# sensorboard.net
KiCad netlist of a schematic drawn in EAGLE
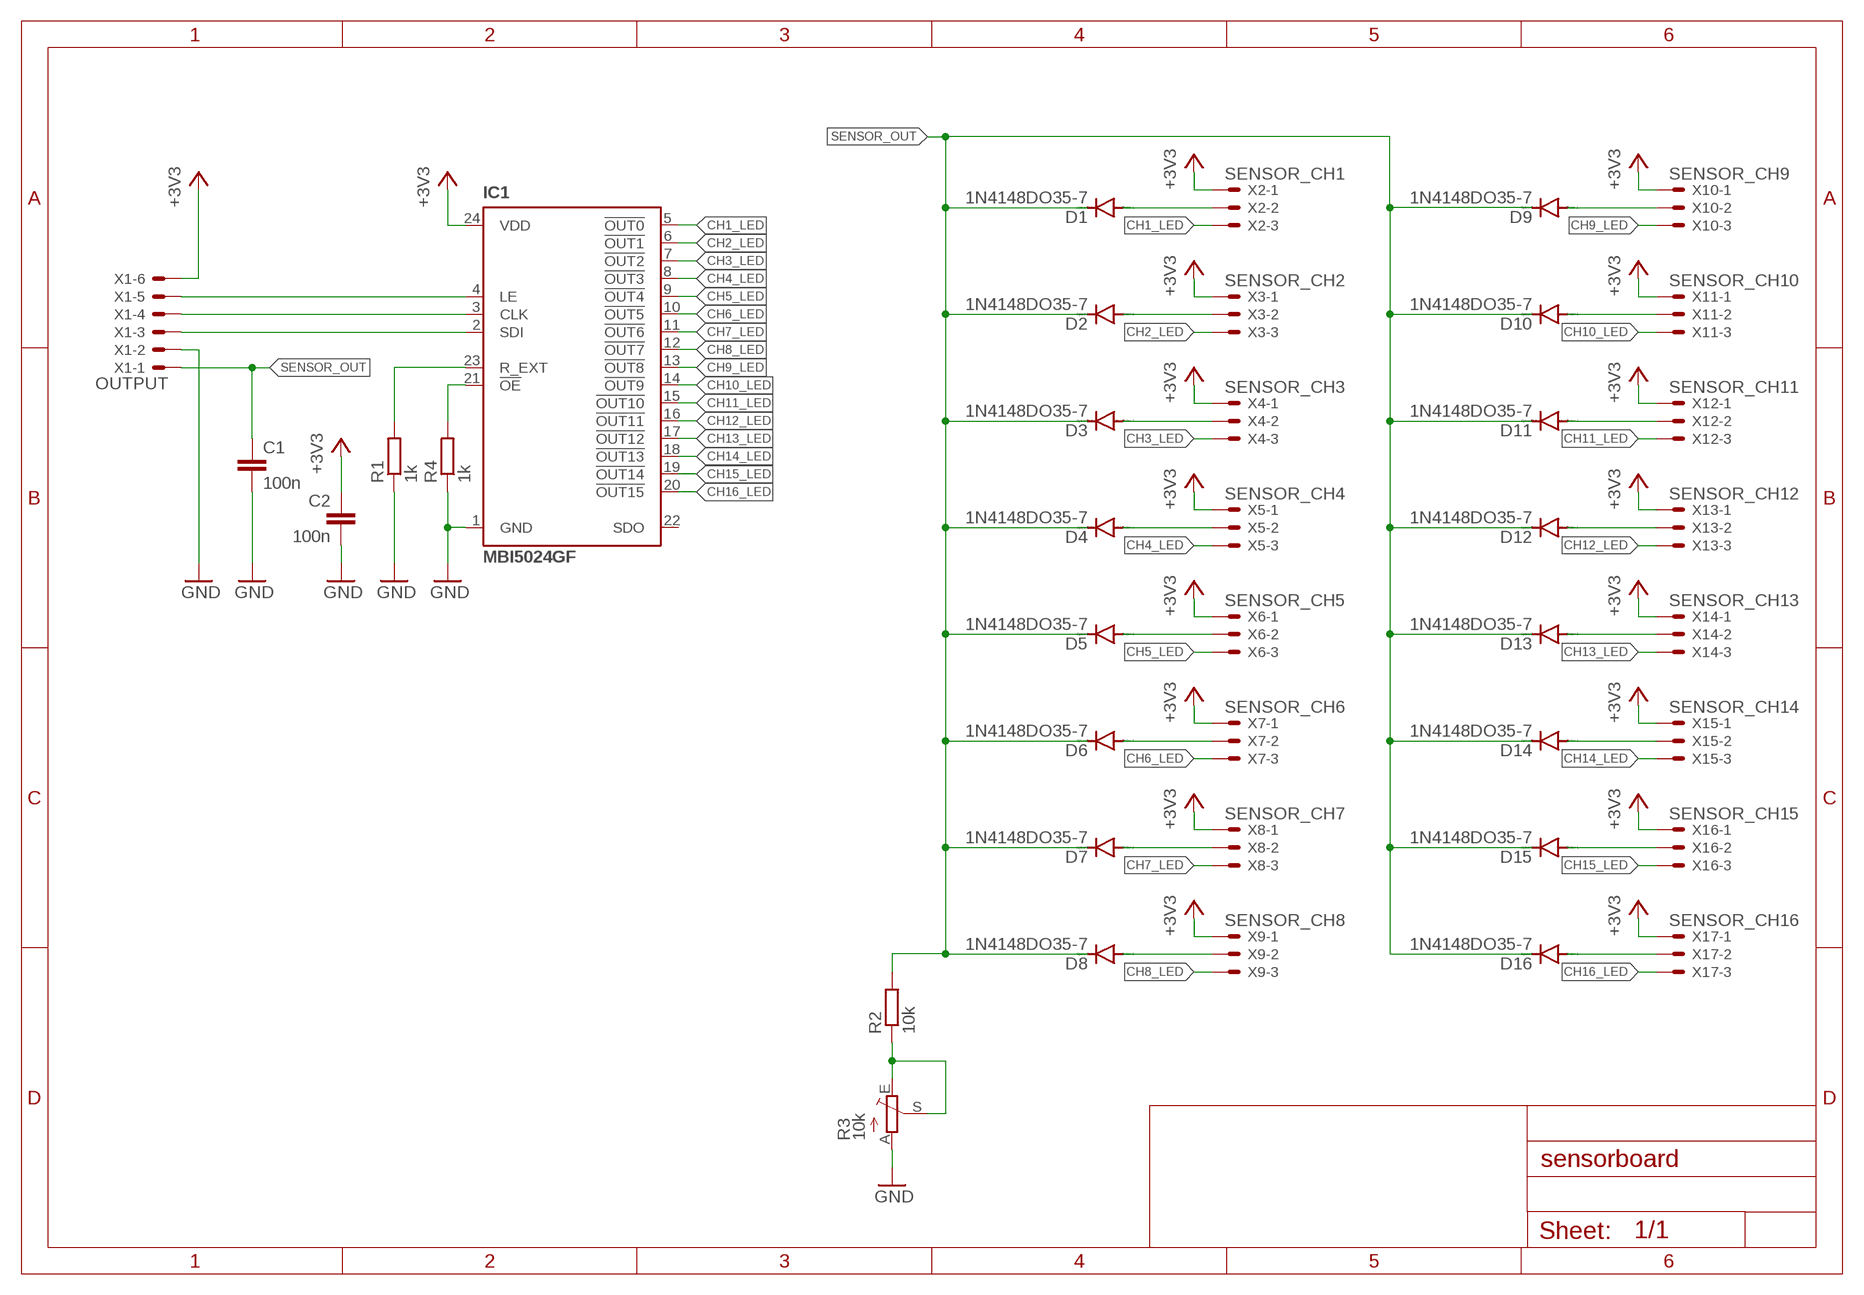
[diagram p0: schematic, sheet 1]

(export (version "E")
  (design (tool "Eeschema 10.0.6"))
  (components
    (comp (ref "C1")
      (value "100n")
      (footprint "eagle-import:C050-024X044")
      (libsource (lib "eagle-import") (part "C-EU050-024X044"))
    )
    (comp (ref "C2")
      (value "100n")
      (footprint "eagle-import:C050-024X044")
      (libsource (lib "eagle-import") (part "C-EU050-024X044"))
    )
    (comp (ref "D1")
      (value "1N4148DO35-7")
      (footprint "eagle-import:DO35-7")
      (libsource (lib "eagle-import") (part "1N4148DO35-7"))
    )
    (comp (ref "D2")
      (value "1N4148DO35-7")
      (footprint "eagle-import:DO35-7")
      (libsource (lib "eagle-import") (part "1N4148DO35-7"))
    )
    (comp (ref "D3")
      (value "1N4148DO35-7")
      (footprint "eagle-import:DO35-7")
      (libsource (lib "eagle-import") (part "1N4148DO35-7"))
    )
    (comp (ref "D4")
      (value "1N4148DO35-7")
      (footprint "eagle-import:DO35-7")
      (libsource (lib "eagle-import") (part "1N4148DO35-7"))
    )
    (comp (ref "D5")
      (value "1N4148DO35-7")
      (footprint "eagle-import:DO35-7")
      (libsource (lib "eagle-import") (part "1N4148DO35-7"))
    )
    (comp (ref "D6")
      (value "1N4148DO35-7")
      (footprint "eagle-import:DO35-7")
      (libsource (lib "eagle-import") (part "1N4148DO35-7"))
    )
    (comp (ref "D7")
      (value "1N4148DO35-7")
      (footprint "eagle-import:DO35-7")
      (libsource (lib "eagle-import") (part "1N4148DO35-7"))
    )
    (comp (ref "D8")
      (value "1N4148DO35-7")
      (footprint "eagle-import:DO35-7")
      (libsource (lib "eagle-import") (part "1N4148DO35-7"))
    )
    (comp (ref "D9")
      (value "1N4148DO35-7")
      (footprint "eagle-import:DO35-7")
      (libsource (lib "eagle-import") (part "1N4148DO35-7"))
    )
    (comp (ref "D10")
      (value "1N4148DO35-7")
      (footprint "eagle-import:DO35-7")
      (libsource (lib "eagle-import") (part "1N4148DO35-7"))
    )
    (comp (ref "D11")
      (value "1N4148DO35-7")
      (footprint "eagle-import:DO35-7")
      (libsource (lib "eagle-import") (part "1N4148DO35-7"))
    )
    (comp (ref "D12")
      (value "1N4148DO35-7")
      (footprint "eagle-import:DO35-7")
      (libsource (lib "eagle-import") (part "1N4148DO35-7"))
    )
    (comp (ref "D13")
      (value "1N4148DO35-7")
      (footprint "eagle-import:DO35-7")
      (libsource (lib "eagle-import") (part "1N4148DO35-7"))
    )
    (comp (ref "D14")
      (value "1N4148DO35-7")
      (footprint "eagle-import:DO35-7")
      (libsource (lib "eagle-import") (part "1N4148DO35-7"))
    )
    (comp (ref "D15")
      (value "1N4148DO35-7")
      (footprint "eagle-import:DO35-7")
      (libsource (lib "eagle-import") (part "1N4148DO35-7"))
    )
    (comp (ref "D16")
      (value "1N4148DO35-7")
      (footprint "eagle-import:DO35-7")
      (libsource (lib "eagle-import") (part "1N4148DO35-7"))
    )
    (comp (ref "IC1")
      (value "MBI5024GF")
      (footprint "eagle-import:24PIN_SOP_ADAPTER")
      (libsource (lib "eagle-import") (part "MBI5024GF"))
    )
    (comp (ref "R1")
      (value "1k")
      (footprint "eagle-import:0207_10")
      (libsource (lib "eagle-import") (part "R-EU_0207/10"))
    )
    (comp (ref "R2")
      (value "10k")
      (footprint "eagle-import:0207_10")
      (libsource (lib "eagle-import") (part "R-EU_0207/10"))
    )
    (comp (ref "R3")
      (value "10k")
      (footprint "eagle-import:CA6V")
      (libsource (lib "eagle-import") (part "TRIM_EU-CA6V"))
    )
    (comp (ref "R4")
      (value "1k")
      (footprint "eagle-import:0207_10")
      (libsource (lib "eagle-import") (part "R-EU_0207/10"))
    )
    (comp (ref "X1")
      (value "OUTPUT")
      (footprint "eagle-import:22-23-2061")
      (fields (field (name "MF") "MOLEX") (field (name "MPN") "22-23-2061"))
      (libsource (lib "eagle-import") (part "22-23-2061"))
    )
    (comp (ref "X2")
      (value "SENSOR_CH1")
      (footprint "eagle-import:22-23-2031")
      (fields (field (name "MF") "MOLEX") (field (name "MPN") "22-23-2031"))
      (libsource (lib "eagle-import") (part "22-23-2031"))
    )
    (comp (ref "X3")
      (value "SENSOR_CH2")
      (footprint "eagle-import:22-23-2031")
      (fields (field (name "MF") "MOLEX") (field (name "MPN") "22-23-2031"))
      (libsource (lib "eagle-import") (part "22-23-2031"))
    )
    (comp (ref "X4")
      (value "SENSOR_CH3")
      (footprint "eagle-import:22-23-2031")
      (fields (field (name "MF") "MOLEX") (field (name "MPN") "22-23-2031"))
      (libsource (lib "eagle-import") (part "22-23-2031"))
    )
    (comp (ref "X5")
      (value "SENSOR_CH4")
      (footprint "eagle-import:22-23-2031")
      (fields (field (name "MF") "MOLEX") (field (name "MPN") "22-23-2031"))
      (libsource (lib "eagle-import") (part "22-23-2031"))
    )
    (comp (ref "X6")
      (value "SENSOR_CH5")
      (footprint "eagle-import:22-23-2031")
      (fields (field (name "MF") "MOLEX") (field (name "MPN") "22-23-2031"))
      (libsource (lib "eagle-import") (part "22-23-2031"))
    )
    (comp (ref "X7")
      (value "SENSOR_CH6")
      (footprint "eagle-import:22-23-2031")
      (fields (field (name "MF") "MOLEX") (field (name "MPN") "22-23-2031"))
      (libsource (lib "eagle-import") (part "22-23-2031"))
    )
    (comp (ref "X8")
      (value "SENSOR_CH7")
      (footprint "eagle-import:22-23-2031")
      (fields (field (name "MF") "MOLEX") (field (name "MPN") "22-23-2031"))
      (libsource (lib "eagle-import") (part "22-23-2031"))
    )
    (comp (ref "X9")
      (value "SENSOR_CH8")
      (footprint "eagle-import:22-23-2031")
      (fields (field (name "MF") "MOLEX") (field (name "MPN") "22-23-2031"))
      (libsource (lib "eagle-import") (part "22-23-2031"))
    )
    (comp (ref "X10")
      (value "SENSOR_CH9")
      (footprint "eagle-import:22-23-2031")
      (fields (field (name "MF") "MOLEX") (field (name "MPN") "22-23-2031"))
      (libsource (lib "eagle-import") (part "22-23-2031"))
    )
    (comp (ref "X11")
      (value "SENSOR_CH10")
      (footprint "eagle-import:22-23-2031")
      (fields (field (name "MF") "MOLEX") (field (name "MPN") "22-23-2031"))
      (libsource (lib "eagle-import") (part "22-23-2031"))
    )
    (comp (ref "X12")
      (value "SENSOR_CH11")
      (footprint "eagle-import:22-23-2031")
      (fields (field (name "MF") "MOLEX") (field (name "MPN") "22-23-2031"))
      (libsource (lib "eagle-import") (part "22-23-2031"))
    )
    (comp (ref "X13")
      (value "SENSOR_CH12")
      (footprint "eagle-import:22-23-2031")
      (fields (field (name "MF") "MOLEX") (field (name "MPN") "22-23-2031"))
      (libsource (lib "eagle-import") (part "22-23-2031"))
    )
    (comp (ref "X14")
      (value "SENSOR_CH13")
      (footprint "eagle-import:22-23-2031")
      (fields (field (name "MF") "MOLEX") (field (name "MPN") "22-23-2031"))
      (libsource (lib "eagle-import") (part "22-23-2031"))
    )
    (comp (ref "X15")
      (value "SENSOR_CH14")
      (footprint "eagle-import:22-23-2031")
      (fields (field (name "MF") "MOLEX") (field (name "MPN") "22-23-2031"))
      (libsource (lib "eagle-import") (part "22-23-2031"))
    )
    (comp (ref "X16")
      (value "SENSOR_CH15")
      (footprint "eagle-import:22-23-2031")
      (fields (field (name "MF") "MOLEX") (field (name "MPN") "22-23-2031"))
      (libsource (lib "eagle-import") (part "22-23-2031"))
    )
    (comp (ref "X17")
      (value "SENSOR_CH16")
      (footprint "eagle-import:22-23-2031")
      (fields (field (name "MF") "MOLEX") (field (name "MPN") "22-23-2031"))
      (libsource (lib "eagle-import") (part "22-23-2031"))
    )
  )
  (nets
    (net (code "1") (name "+3V3") (class "Default")
      (node (ref "C2") (pin "1") (pinfunction "1_1") (pintype "passive"))
      (node (ref "IC1") (pin "24") (pinfunction "VDD_24") (pintype "bidirectional"))
      (node (ref "X1") (pin "6") (pinfunction "S_6") (pintype "passive"))
      (node (ref "X10") (pin "1") (pinfunction "S_1") (pintype "passive"))
      (node (ref "X11") (pin "1") (pinfunction "S_1") (pintype "passive"))
      (node (ref "X12") (pin "1") (pinfunction "S_1") (pintype "passive"))
      (node (ref "X13") (pin "1") (pinfunction "S_1") (pintype "passive"))
      (node (ref "X14") (pin "1") (pinfunction "S_1") (pintype "passive"))
      (node (ref "X15") (pin "1") (pinfunction "S_1") (pintype "passive"))
      (node (ref "X16") (pin "1") (pinfunction "S_1") (pintype "passive"))
      (node (ref "X17") (pin "1") (pinfunction "S_1") (pintype "passive"))
      (node (ref "X2") (pin "1") (pinfunction "S_1") (pintype "passive"))
      (node (ref "X3") (pin "1") (pinfunction "S_1") (pintype "passive"))
      (node (ref "X4") (pin "1") (pinfunction "S_1") (pintype "passive"))
      (node (ref "X5") (pin "1") (pinfunction "S_1") (pintype "passive"))
      (node (ref "X6") (pin "1") (pinfunction "S_1") (pintype "passive"))
      (node (ref "X7") (pin "1") (pinfunction "S_1") (pintype "passive"))
      (node (ref "X8") (pin "1") (pinfunction "S_1") (pintype "passive"))
      (node (ref "X9") (pin "1") (pinfunction "S_1") (pintype "passive"))
    )
    (net (code "2") (name "CH1_LED") (class "Default")
      (node (ref "IC1") (pin "5") (pinfunction "~{OUT0}_5") (pintype "bidirectional"))
      (node (ref "X2") (pin "3") (pinfunction "S_3") (pintype "passive"))
    )
    (net (code "3") (name "CH2_LED") (class "Default")
      (node (ref "IC1") (pin "6") (pinfunction "~{OUT1}_6") (pintype "bidirectional"))
      (node (ref "X3") (pin "3") (pinfunction "S_3") (pintype "passive"))
    )
    (net (code "4") (name "CH3_LED") (class "Default")
      (node (ref "IC1") (pin "7") (pinfunction "~{OUT2}_7") (pintype "bidirectional"))
      (node (ref "X4") (pin "3") (pinfunction "S_3") (pintype "passive"))
    )
    (net (code "5") (name "CH4_LED") (class "Default")
      (node (ref "IC1") (pin "8") (pinfunction "~{OUT3}_8") (pintype "bidirectional"))
      (node (ref "X5") (pin "3") (pinfunction "S_3") (pintype "passive"))
    )
    (net (code "6") (name "CH5_LED") (class "Default")
      (node (ref "IC1") (pin "9") (pinfunction "~{OUT4}_9") (pintype "bidirectional"))
      (node (ref "X6") (pin "3") (pinfunction "S_3") (pintype "passive"))
    )
    (net (code "7") (name "CH6_LED") (class "Default")
      (node (ref "IC1") (pin "10") (pinfunction "~{OUT5}_10") (pintype "bidirectional"))
      (node (ref "X7") (pin "3") (pinfunction "S_3") (pintype "passive"))
    )
    (net (code "8") (name "CH7_LED") (class "Default")
      (node (ref "IC1") (pin "11") (pinfunction "~{OUT6}_11") (pintype "bidirectional"))
      (node (ref "X8") (pin "3") (pinfunction "S_3") (pintype "passive"))
    )
    (net (code "9") (name "CH8_LED") (class "Default")
      (node (ref "IC1") (pin "12") (pinfunction "~{OUT7}_12") (pintype "bidirectional"))
      (node (ref "X9") (pin "3") (pinfunction "S_3") (pintype "passive"))
    )
    (net (code "10") (name "CH9_LED") (class "Default")
      (node (ref "IC1") (pin "13") (pinfunction "~{OUT8}_13") (pintype "bidirectional"))
      (node (ref "X10") (pin "3") (pinfunction "S_3") (pintype "passive"))
    )
    (net (code "11") (name "CH10_LED") (class "Default")
      (node (ref "IC1") (pin "14") (pinfunction "~{OUT9}_14") (pintype "bidirectional"))
      (node (ref "X11") (pin "3") (pinfunction "S_3") (pintype "passive"))
    )
    (net (code "12") (name "CH11_LED") (class "Default")
      (node (ref "IC1") (pin "15") (pinfunction "~{OUT10}_15") (pintype "bidirectional"))
      (node (ref "X12") (pin "3") (pinfunction "S_3") (pintype "passive"))
    )
    (net (code "13") (name "CH12_LED") (class "Default")
      (node (ref "IC1") (pin "16") (pinfunction "~{OUT11}_16") (pintype "bidirectional"))
      (node (ref "X13") (pin "3") (pinfunction "S_3") (pintype "passive"))
    )
    (net (code "14") (name "CH13_LED") (class "Default")
      (node (ref "IC1") (pin "17") (pinfunction "~{OUT12}_17") (pintype "bidirectional"))
      (node (ref "X14") (pin "3") (pinfunction "S_3") (pintype "passive"))
    )
    (net (code "15") (name "CH14_LED") (class "Default")
      (node (ref "IC1") (pin "18") (pinfunction "~{OUT13}_18") (pintype "bidirectional"))
      (node (ref "X15") (pin "3") (pinfunction "S_3") (pintype "passive"))
    )
    (net (code "16") (name "CH15_LED") (class "Default")
      (node (ref "IC1") (pin "19") (pinfunction "~{OUT14}_19") (pintype "bidirectional"))
      (node (ref "X16") (pin "3") (pinfunction "S_3") (pintype "passive"))
    )
    (net (code "17") (name "CH16_LED") (class "Default")
      (node (ref "IC1") (pin "20") (pinfunction "~{OUT15}_20") (pintype "bidirectional"))
      (node (ref "X17") (pin "3") (pinfunction "S_3") (pintype "passive"))
    )
    (net (code "18") (name "GND") (class "Default")
      (node (ref "C1") (pin "2") (pinfunction "2_2") (pintype "passive"))
      (node (ref "C2") (pin "2") (pinfunction "2_2") (pintype "passive"))
      (node (ref "IC1") (pin "1") (pinfunction "GND_1") (pintype "bidirectional"))
      (node (ref "R1") (pin "1") (pinfunction "1_1") (pintype "passive"))
      (node (ref "R3") (pin "A") (pinfunction "A_A") (pintype "passive"))
      (node (ref "R4") (pin "1") (pinfunction "1_1") (pintype "passive"))
      (node (ref "X1") (pin "2") (pinfunction "S_2") (pintype "passive"))
    )
    (net (code "19") (name "Net-(IC1-CLK)") (class "Default")
      (node (ref "IC1") (pin "3") (pinfunction "CLK_3") (pintype "bidirectional"))
      (node (ref "X1") (pin "4") (pinfunction "S_4") (pintype "passive"))
    )
    (net (code "20") (name "Net-(IC1-LE)") (class "Default")
      (node (ref "IC1") (pin "4") (pinfunction "LE_4") (pintype "bidirectional"))
      (node (ref "X1") (pin "5") (pinfunction "S_5") (pintype "passive"))
    )
    (net (code "21") (name "Net-(IC1-R_EXT)") (class "Default")
      (node (ref "IC1") (pin "23") (pinfunction "R_EXT_23") (pintype "bidirectional"))
      (node (ref "R1") (pin "2") (pinfunction "2_2") (pintype "passive"))
    )
    (net (code "22") (name "Net-(IC1-SDI)") (class "Default")
      (node (ref "IC1") (pin "2") (pinfunction "SDI_2") (pintype "bidirectional"))
      (node (ref "X1") (pin "3") (pinfunction "S_3") (pintype "passive"))
    )
    (net (code "23") (name "Net-(IC1-~{OE})") (class "Default")
      (node (ref "IC1") (pin "21") (pinfunction "~{OE}_21") (pintype "bidirectional"))
      (node (ref "R4") (pin "2") (pinfunction "2_2") (pintype "passive"))
    )
    (net (code "24") (name "Net-(R2-Pad1)") (class "Default")
      (node (ref "R2") (pin "1") (pinfunction "1_1") (pintype "passive"))
      (node (ref "R3") (pin "E") (pinfunction "E_E") (pintype "passive"))
      (node (ref "R3") (pin "S") (pinfunction "S_S") (pintype "passive"))
    )
    (net (code "25") (name "Net-(X2B-S)") (class "Default")
      (node (ref "D1") (pin "A") (pinfunction "A_A") (pintype "passive"))
      (node (ref "X2") (pin "2") (pinfunction "S_2") (pintype "passive"))
    )
    (net (code "26") (name "Net-(X3B-S)") (class "Default")
      (node (ref "D2") (pin "A") (pinfunction "A_A") (pintype "passive"))
      (node (ref "X3") (pin "2") (pinfunction "S_2") (pintype "passive"))
    )
    (net (code "27") (name "Net-(X4B-S)") (class "Default")
      (node (ref "D3") (pin "A") (pinfunction "A_A") (pintype "passive"))
      (node (ref "X4") (pin "2") (pinfunction "S_2") (pintype "passive"))
    )
    (net (code "28") (name "Net-(X5B-S)") (class "Default")
      (node (ref "D4") (pin "A") (pinfunction "A_A") (pintype "passive"))
      (node (ref "X5") (pin "2") (pinfunction "S_2") (pintype "passive"))
    )
    (net (code "29") (name "Net-(X6B-S)") (class "Default")
      (node (ref "D5") (pin "A") (pinfunction "A_A") (pintype "passive"))
      (node (ref "X6") (pin "2") (pinfunction "S_2") (pintype "passive"))
    )
    (net (code "30") (name "Net-(X7B-S)") (class "Default")
      (node (ref "D6") (pin "A") (pinfunction "A_A") (pintype "passive"))
      (node (ref "X7") (pin "2") (pinfunction "S_2") (pintype "passive"))
    )
    (net (code "31") (name "Net-(X8B-S)") (class "Default")
      (node (ref "D7") (pin "A") (pinfunction "A_A") (pintype "passive"))
      (node (ref "X8") (pin "2") (pinfunction "S_2") (pintype "passive"))
    )
    (net (code "32") (name "Net-(X9B-S)") (class "Default")
      (node (ref "D8") (pin "A") (pinfunction "A_A") (pintype "passive"))
      (node (ref "X9") (pin "2") (pinfunction "S_2") (pintype "passive"))
    )
    (net (code "33") (name "Net-(X10B-S)") (class "Default")
      (node (ref "D9") (pin "A") (pinfunction "A_A") (pintype "passive"))
      (node (ref "X10") (pin "2") (pinfunction "S_2") (pintype "passive"))
    )
    (net (code "34") (name "Net-(X11B-S)") (class "Default")
      (node (ref "D10") (pin "A") (pinfunction "A_A") (pintype "passive"))
      (node (ref "X11") (pin "2") (pinfunction "S_2") (pintype "passive"))
    )
    (net (code "35") (name "Net-(X12B-S)") (class "Default")
      (node (ref "D11") (pin "A") (pinfunction "A_A") (pintype "passive"))
      (node (ref "X12") (pin "2") (pinfunction "S_2") (pintype "passive"))
    )
    (net (code "36") (name "Net-(X13B-S)") (class "Default")
      (node (ref "D12") (pin "A") (pinfunction "A_A") (pintype "passive"))
      (node (ref "X13") (pin "2") (pinfunction "S_2") (pintype "passive"))
    )
    (net (code "37") (name "Net-(X14B-S)") (class "Default")
      (node (ref "D13") (pin "A") (pinfunction "A_A") (pintype "passive"))
      (node (ref "X14") (pin "2") (pinfunction "S_2") (pintype "passive"))
    )
    (net (code "38") (name "Net-(X15B-S)") (class "Default")
      (node (ref "D14") (pin "A") (pinfunction "A_A") (pintype "passive"))
      (node (ref "X15") (pin "2") (pinfunction "S_2") (pintype "passive"))
    )
    (net (code "39") (name "Net-(X16B-S)") (class "Default")
      (node (ref "D15") (pin "A") (pinfunction "A_A") (pintype "passive"))
      (node (ref "X16") (pin "2") (pinfunction "S_2") (pintype "passive"))
    )
    (net (code "40") (name "Net-(X17B-S)") (class "Default")
      (node (ref "D16") (pin "A") (pinfunction "A_A") (pintype "passive"))
      (node (ref "X17") (pin "2") (pinfunction "S_2") (pintype "passive"))
    )
    (net (code "41") (name "SENSOR_OUT") (class "Default")
      (node (ref "C1") (pin "1") (pinfunction "1_1") (pintype "passive"))
      (node (ref "D1") (pin "C") (pinfunction "C_C") (pintype "passive"))
      (node (ref "D10") (pin "C") (pinfunction "C_C") (pintype "passive"))
      (node (ref "D11") (pin "C") (pinfunction "C_C") (pintype "passive"))
      (node (ref "D12") (pin "C") (pinfunction "C_C") (pintype "passive"))
      (node (ref "D13") (pin "C") (pinfunction "C_C") (pintype "passive"))
      (node (ref "D14") (pin "C") (pinfunction "C_C") (pintype "passive"))
      (node (ref "D15") (pin "C") (pinfunction "C_C") (pintype "passive"))
      (node (ref "D16") (pin "C") (pinfunction "C_C") (pintype "passive"))
      (node (ref "D2") (pin "C") (pinfunction "C_C") (pintype "passive"))
      (node (ref "D3") (pin "C") (pinfunction "C_C") (pintype "passive"))
      (node (ref "D4") (pin "C") (pinfunction "C_C") (pintype "passive"))
      (node (ref "D5") (pin "C") (pinfunction "C_C") (pintype "passive"))
      (node (ref "D6") (pin "C") (pinfunction "C_C") (pintype "passive"))
      (node (ref "D7") (pin "C") (pinfunction "C_C") (pintype "passive"))
      (node (ref "D8") (pin "C") (pinfunction "C_C") (pintype "passive"))
      (node (ref "D9") (pin "C") (pinfunction "C_C") (pintype "passive"))
      (node (ref "R2") (pin "2") (pinfunction "2_2") (pintype "passive"))
      (node (ref "X1") (pin "1") (pinfunction "S_1") (pintype "passive"))
    )
    (net (code "42") (name "unconnected-(IC1-SDO-Pad22)") (class "Default")
      (node (ref "IC1") (pin "22") (pinfunction "SDO_22") (pintype "bidirectional"))
    )
  )
)
